# Limit_Switch_Bottom_Horizontal_v1_0.net
KiCad netlist of a schematic drawn in Altium Designer
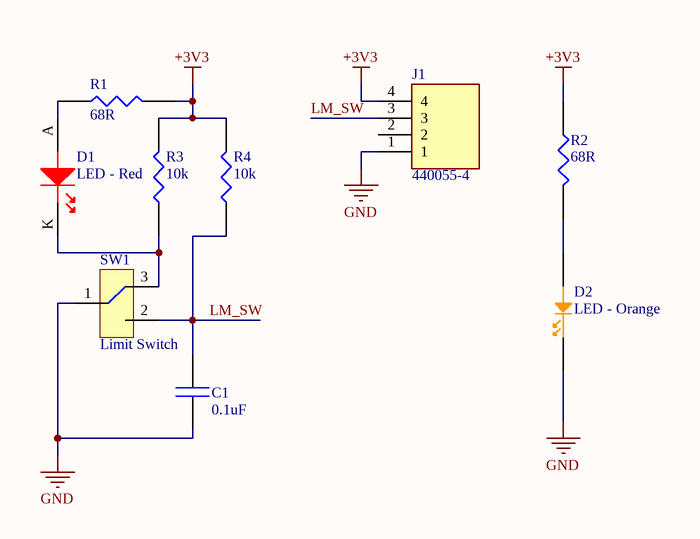
[diagram p0: Limit_Switch_Bottom_Horizontal_v1.0.SchDoc]

(export (version "E")
  (design (tool "Eeschema 10.0.6"))
  (components
    (comp (ref "C1")
      (value "0.1uF")
      (footprint "0.1uF 0603")
      (description "CAP CER 0.1UF 16V X7R 0603")
      (fields
        (field (name "MANUFACTURER") "KEMET")
        (field (name "MANUFACTURER PART NUMBER") "C0603C104M4RACTU")
      )
      (libsource (lib "Limit_Switch") (part "C0603C104M4RACTU"))
    )
    (comp (ref "D1")
      (value "LED - Red")
      (footprint "LED 5MM")
      (description "LED RED CLEAR 5MM OVAL T/H")
      (fields
        (field (name "MANUFACTURER") "Cree")
        (field (name "MANUFACTURER PART NUMBER") "C5SMF-RJF-CT0W0BB2")
      )
      (libsource (lib "5mm Red LED") (part "C5SMF-RJF-CT0W0BB2"))
    )
    (comp (ref "D2")
      (value "LED - Orange")
      (footprint "LED0603-Orange")
      (description "LED ORANGE CLEAR SMD")
      (fields
        (field (name "MANUFACTURER") "Vishay Lite-On")
        (field (name "MANUFACTURER PART NUMBER") "LTST-C191KFKT")
      )
      (libsource (lib "Limit_Switch") (part "LTST-C191KFKT"))
    )
    (comp (ref "J1")
      (value "440055-4")
      (footprint "TE_440055-4")
      (description "2.0MM,HDR,4POS,R/A")
      (fields (field (name "MF") "TE Connectivity"))
      (libsource (lib "440055-4 (1)") (part "440055-4"))
    )
    (comp (ref "R1")
      (value "68R")
      (footprint "68R 0603")
      (description "CRGP 0603 68R 1%")
      (fields
        (field (name "MANUFACTURER") "TE Connectivity")
        (field (name "MANUFACTURER PART NUMBER") "CRGP0603F68R")
      )
      (libsource (lib "Limit_Switch") (part "CRGP0603F68R"))
    )
    (comp (ref "R2")
      (value "68R")
      (footprint "68R 0603")
      (description "CRGP 0603 68R 1%")
      (fields
        (field (name "MANUFACTURER") "TE Connectivity")
        (field (name "MANUFACTURER PART NUMBER") "CRGP0603F68R")
      )
      (libsource (lib "Limit_Switch") (part "CRGP0603F68R"))
    )
    (comp (ref "R3")
      (value "10k")
      (footprint "10k R0603")
      (description "RES 10.0K OHM 1/10W 1% 0603")
      (fields
        (field (name "MANUFACTURER") "TE Connectivity")
        (field (name "MANUFACTURER PART NUMBER") "CRG0603F10K/10")
      )
      (libsource (lib "Limit_Switch") (part "CRG0603F10K/10"))
    )
    (comp (ref "R4")
      (value "10k")
      (footprint "10k R0603")
      (description "RES 10.0K OHM 1/10W 1% 0603")
      (fields
        (field (name "MANUFACTURER") "TE Connectivity")
        (field (name "MANUFACTURER PART NUMBER") "CRG0603F10K/10")
      )
      (libsource (lib "Limit_Switch") (part "CRG0603F10K/10"))
    )
    (comp (ref "SW1")
      (value "Limit Switch")
      (footprint "LIM SW 1")
      (description "SWITCH SNAP ACT SPDT 100MA 125V")
      (fields
        (field (name "MANUFACTURER") "E-Switch")
        (field (name "MANUFACTURER PART NUMBER") "SS075Q102F035V2A")
      )
      (libsource (lib "Limit_Switch_RGB") (part "SS075Q102F035V2A"))
    )
  )
  (nets
    (net (code "1") (name "+3V3") (class "Default")
      (node (ref "J1") (pin "4") (pinfunction "4_4") (pintype "passive"))
      (node (ref "R1") (pin "2") (pinfunction "2_2") (pintype "passive"))
      (node (ref "R2") (pin "1") (pinfunction "1_1") (pintype "passive"))
      (node (ref "R3") (pin "2") (pinfunction "2_2") (pintype "passive"))
      (node (ref "R4") (pin "2") (pinfunction "2_2") (pintype "passive"))
    )
    (net (code "2") (name "/LM_SW") (class "Default")
      (node (ref "C1") (pin "2") (pinfunction "2_2") (pintype "passive"))
      (node (ref "J1") (pin "3") (pinfunction "3_3") (pintype "passive"))
      (node (ref "R4") (pin "1") (pinfunction "1_1") (pintype "passive"))
      (node (ref "SW1") (pin "2") (pinfunction "NO_2") (pintype "passive"))
    )
    (net (code "3") (name "GND") (class "Default")
      (node (ref "C1") (pin "1") (pinfunction "1_1") (pintype "passive"))
      (node (ref "D2") (pin "1") (pinfunction "Cathode_1") (pintype "passive"))
      (node (ref "J1") (pin "1") (pinfunction "1_1") (pintype "passive"))
      (node (ref "SW1") (pin "1") (pinfunction "COM_1") (pintype "passive"))
    )
    (net (code "4") (name "Net-(D1-Anode)") (class "Default")
      (node (ref "D1") (pin "A") (pinfunction "Anode_A") (pintype "passive"))
      (node (ref "R1") (pin "1") (pinfunction "1_1") (pintype "passive"))
    )
    (net (code "5") (name "Net-(D1-Cathode)") (class "Default")
      (node (ref "D1") (pin "K") (pinfunction "Cathode_K") (pintype "passive"))
      (node (ref "R3") (pin "1") (pinfunction "1_1") (pintype "passive"))
      (node (ref "SW1") (pin "3") (pinfunction "NC_3") (pintype "passive"))
    )
    (net (code "6") (name "Net-(D2-Anode)") (class "Default")
      (node (ref "D2") (pin "2") (pinfunction "Anode_2") (pintype "passive"))
      (node (ref "R2") (pin "2") (pinfunction "2_2") (pintype "passive"))
    )
    (net (code "7") (name "unconnected-(J1-Pad2)") (class "Default")
      (node (ref "J1") (pin "2") (pinfunction "2_2") (pintype "passive"))
    )
  )
)
